# RelayDetect2_V2.net
KiCad netlist of a schematic drawn in Altium Designer
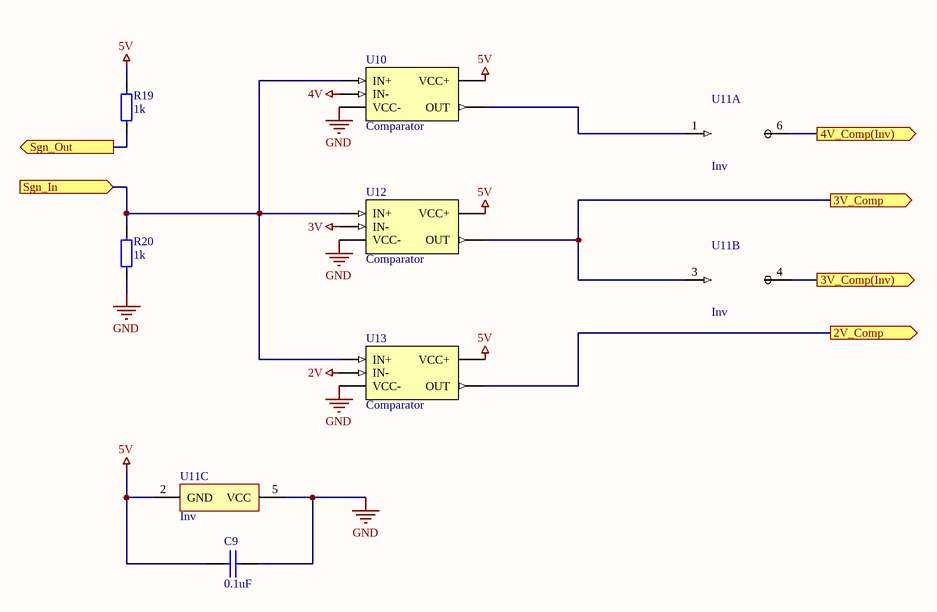
[diagram p0: RelayDetect2 V2.SchDoc]

(export (version "E")
  (design (tool "Eeschema 10.0.6"))
  (components
    (comp (ref "C9")
      (value "0.1uF")
      (footprint "0805 Capicator")
      (description "0.1uF X7R 50V 10% 0805")
      (fields
        (field (name "MANUFACTURER") "Murata Manufacturing")
        (field (name "PART NUMBER") "GRM21BR71E104KA01L")
      )
      (libsource (lib "BRT_Components") (part "Cap 0.1uF (0805)"))
    )
    (comp (ref "R19")
      (value "1k")
      (footprint "0603 Resistor")
      (description "0.1W 0603 1k, 1%")
      (fields (field (name "PART NUMBER") "RC0603FR-071KL") (field (name "MANUFACTURER") "Taiwan"))
      (libsource (lib "BRT_Components") (part "Res 1k (0603)"))
    )
    (comp (ref "R20")
      (value "1k")
      (footprint "0603 Resistor")
      (description "0.1W 0603 1k, 1%")
      (fields (field (name "PART NUMBER") "RC0603FR-071KL") (field (name "MANUFACTURER") "Taiwan"))
      (libsource (lib "BRT_Components") (part "Res 1k (0603)"))
    )
    (comp (ref "U10")
      (value "Comparator")
      (footprint "SOT-23-5")
      (description "LMV7219 7-ns 2.7-V to 5-V Comparator with Rail-to-Rail Output")
      (fields
        (field (name "PART NUMBER") "LMV7219M5X/NOPB")
        (field (name "MANUFACTURER") "Texas Instruments")
      )
      (libsource (lib "BRT_Components") (part "Comparator [LMV]"))
    )
    (comp (ref "U11") (value "Inv") (footprint "SOT236") (libsource (lib "TSAL") (part "Inverter")))
    (comp (ref "U12")
      (value "Comparator")
      (footprint "SOT-23-5")
      (description "LMV7219 7-ns 2.7-V to 5-V Comparator with Rail-to-Rail Output")
      (fields
        (field (name "PART NUMBER") "LMV7219M5X/NOPB")
        (field (name "MANUFACTURER") "Texas Instruments")
      )
      (libsource (lib "BRT_Components") (part "Comparator [LMV]"))
    )
    (comp (ref "U13")
      (value "Comparator")
      (footprint "SOT-23-5")
      (description "LMV7219 7-ns 2.7-V to 5-V Comparator with Rail-to-Rail Output")
      (fields
        (field (name "PART NUMBER") "LMV7219M5X/NOPB")
        (field (name "MANUFACTURER") "Texas Instruments")
      )
      (libsource (lib "BRT_Components") (part "Comparator [LMV]"))
    )
  )
  (nets
    (net (code "1") (name "/2V_Comp") (class "Default")
      (node (ref "U13") (pin "1") (pinfunction "OUT_1") (pintype "output"))
    )
    (net (code "2") (name "/3V_Comp") (class "Default")
      (node (ref "U11") (pin "3") (pinfunction "A_3") (pintype "input"))
      (node (ref "U12") (pin "1") (pinfunction "OUT_1") (pintype "output"))
    )
    (net (code "3") (name "/3V_Comp(Inv)") (class "Default")
      (node (ref "U11") (pin "4") (pinfunction "Y_4") (pintype "passive"))
    )
    (net (code "4") (name "/4V_Comp(Inv)") (class "Default")
      (node (ref "U11") (pin "6") (pinfunction "Y_6") (pintype "passive"))
    )
    (net (code "5") (name "/Sgn_In") (class "Default")
      (node (ref "R20") (pin "2") (pinfunction "2_2") (pintype "passive"))
      (node (ref "U10") (pin "3") (pinfunction "IN+_3") (pintype "input"))
      (node (ref "U12") (pin "3") (pinfunction "IN+_3") (pintype "input"))
      (node (ref "U13") (pin "3") (pinfunction "IN+_3") (pintype "input"))
    )
    (net (code "6") (name "/Sgn_Out") (class "Default")
      (node (ref "R19") (pin "1") (pinfunction "1_1") (pintype "passive"))
    )
    (net (code "7") (name "2V") (class "Default")
      (node (ref "U13") (pin "4") (pinfunction "IN-_4") (pintype "input"))
    )
    (net (code "8") (name "3V") (class "Default")
      (node (ref "U12") (pin "4") (pinfunction "IN-_4") (pintype "input"))
    )
    (net (code "9") (name "4V") (class "Default")
      (node (ref "U10") (pin "4") (pinfunction "IN-_4") (pintype "input"))
    )
    (net (code "10") (name "5V") (class "Default")
      (node (ref "C9") (pin "1") (pinfunction "1_1") (pintype "passive"))
      (node (ref "R19") (pin "2") (pinfunction "2_2") (pintype "passive"))
      (node (ref "U10") (pin "5") (pinfunction "VCC+_5") (pintype "power_in"))
      (node (ref "U11") (pin "2") (pinfunction "GND_2") (pintype "passive"))
      (node (ref "U12") (pin "5") (pinfunction "VCC+_5") (pintype "power_in"))
      (node (ref "U13") (pin "5") (pinfunction "VCC+_5") (pintype "power_in"))
    )
    (net (code "11") (name "GND") (class "Default")
      (node (ref "C9") (pin "2") (pinfunction "2_2") (pintype "passive"))
      (node (ref "R20") (pin "1") (pinfunction "1_1") (pintype "passive"))
      (node (ref "U10") (pin "2") (pinfunction "VCC-_2") (pintype "power_in"))
      (node (ref "U11") (pin "5") (pinfunction "VCC_5") (pintype "passive"))
      (node (ref "U12") (pin "2") (pinfunction "VCC-_2") (pintype "power_in"))
      (node (ref "U13") (pin "2") (pinfunction "VCC-_2") (pintype "power_in"))
    )
    (net (code "12") (name "Net-(U10-OUT)") (class "Default")
      (node (ref "U10") (pin "1") (pinfunction "OUT_1") (pintype "output"))
      (node (ref "U11") (pin "1") (pinfunction "A_1") (pintype "input"))
    )
  )
)
